# murdock_conn_v3.net
KiCad netlist of a schematic drawn in EAGLE
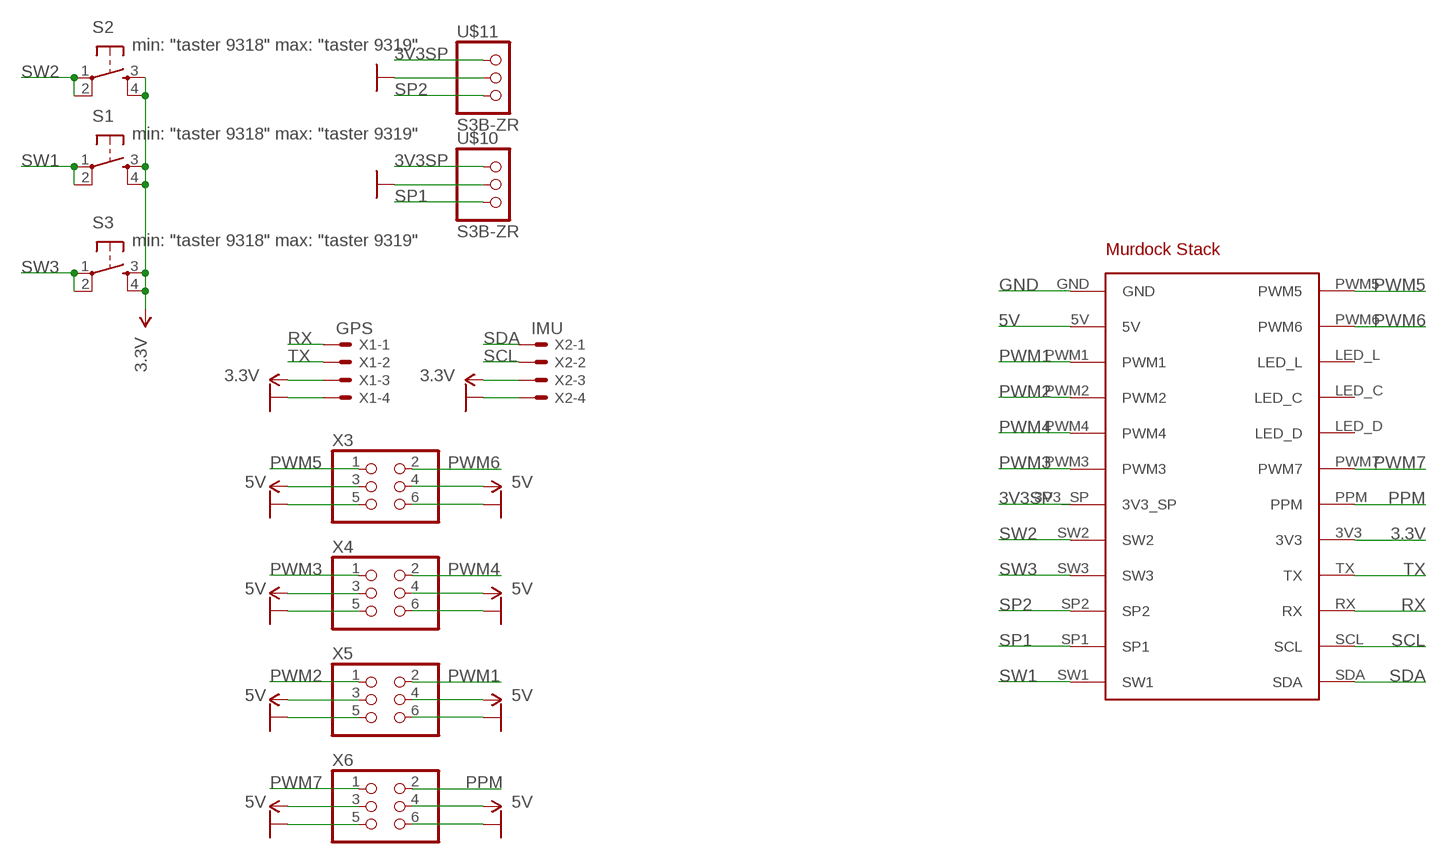
[diagram p0: schematic, sheet 1]

(export (version "E")
  (design (tool "Eeschema 10.0.6"))
  (components
    (comp (ref "S1")
      (value "min: \"taster 9318\" max: \"taster 9319\"")
      (footprint "eagle-import:LSH")
      (libsource (lib "eagle-import") (part "LSH"))
    )
    (comp (ref "S2")
      (value "min: \"taster 9318\" max: \"taster 9319\"")
      (footprint "eagle-import:LSH")
      (libsource (lib "eagle-import") (part "LSH"))
    )
    (comp (ref "S3")
      (value "min: \"taster 9318\" max: \"taster 9319\"")
      (footprint "eagle-import:LSH")
      (libsource (lib "eagle-import") (part "LSH"))
    )
    (comp (ref "U$10")
      (value "S3B-ZR")
      (footprint "eagle-import:S3B-ZR")
      (libsource (lib "eagle-import") (part "S3B-ZR"))
    )
    (comp (ref "U$11")
      (value "S3B-ZR")
      (footprint "eagle-import:S3B-ZR")
      (libsource (lib "eagle-import") (part "S3B-ZR"))
    )
    (comp (ref "X1")
      (value "GPS")
      (footprint "eagle-import:70553-04")
      (libsource (lib "eagle-import") (part "C-GRID-04-70553"))
    )
    (comp (ref "X2")
      (value "IMU")
      (footprint "eagle-import:70553-04")
      (libsource (lib "eagle-import") (part "C-GRID-04-70553"))
    )
    (comp (ref "X3")
      (value "PINHD-2X3/90")
      (footprint "eagle-import:2X03_90")
      (libsource (lib "eagle-import") (part "PINHD-2X3/90"))
    )
    (comp (ref "X4")
      (value "PINHD-2X3/90")
      (footprint "eagle-import:2X03_90")
      (libsource (lib "eagle-import") (part "PINHD-2X3/90"))
    )
    (comp (ref "X5")
      (value "PINHD-2X3/90")
      (footprint "eagle-import:2X03_90")
      (libsource (lib "eagle-import") (part "PINHD-2X3/90"))
    )
    (comp (ref "X6")
      (value "PINHD-2X3/90")
      (footprint "eagle-import:2X03_90")
      (libsource (lib "eagle-import") (part "PINHD-2X3/90"))
    )
    (comp (ref "X7")
      (value "MURDOCK_STACK")
      (footprint "eagle-import:MURDOCK_STACK")
      (libsource (lib "eagle-import") (part "MURDOCK_STACK"))
    )
  )
  (nets
    (net (code "1") (name "/3V3SP") (class "Default")
      (node (ref "U$10") (pin "1") (pinfunction "1_1") (pintype "bidirectional"))
      (node (ref "U$11") (pin "1") (pinfunction "1_1") (pintype "bidirectional"))
      (node (ref "X7") (pin "3V3_SP") (pinfunction "3V3_SP_3V3_SP") (pintype "bidirectional"))
    )
    (net (code "2") (name "/PPM") (class "Default")
      (node (ref "X6") (pin "2") (pinfunction "2_2") (pintype "passive"))
      (node (ref "X7") (pin "PPM") (pinfunction "PPM_PPM") (pintype "bidirectional"))
    )
    (net (code "3") (name "/PWM1") (class "Default")
      (node (ref "X5") (pin "2") (pinfunction "2_2") (pintype "passive"))
      (node (ref "X7") (pin "PWM1") (pinfunction "PWM1_PWM1") (pintype "bidirectional"))
    )
    (net (code "4") (name "/PWM2") (class "Default")
      (node (ref "X5") (pin "1") (pinfunction "1_1") (pintype "passive"))
      (node (ref "X7") (pin "PWM2") (pinfunction "PWM2_PWM2") (pintype "bidirectional"))
    )
    (net (code "5") (name "/PWM3") (class "Default")
      (node (ref "X4") (pin "1") (pinfunction "1_1") (pintype "passive"))
      (node (ref "X7") (pin "PWM3") (pinfunction "PWM3_PWM3") (pintype "bidirectional"))
    )
    (net (code "6") (name "/PWM4") (class "Default")
      (node (ref "X4") (pin "2") (pinfunction "2_2") (pintype "passive"))
      (node (ref "X7") (pin "PWM4") (pinfunction "PWM4_PWM4") (pintype "bidirectional"))
    )
    (net (code "7") (name "/PWM5") (class "Default")
      (node (ref "X3") (pin "1") (pinfunction "1_1") (pintype "passive"))
      (node (ref "X7") (pin "PWM5") (pinfunction "PWM5_PWM5") (pintype "bidirectional"))
    )
    (net (code "8") (name "/PWM6") (class "Default")
      (node (ref "X3") (pin "2") (pinfunction "2_2") (pintype "passive"))
      (node (ref "X7") (pin "PWM6") (pinfunction "PWM6_PWM6") (pintype "bidirectional"))
    )
    (net (code "9") (name "/PWM7") (class "Default")
      (node (ref "X6") (pin "1") (pinfunction "1_1") (pintype "passive"))
      (node (ref "X7") (pin "PWM7") (pinfunction "PWM7_PWM7") (pintype "bidirectional"))
    )
    (net (code "10") (name "/RX") (class "Default")
      (node (ref "X1") (pin "1") (pinfunction "S_1") (pintype "passive"))
      (node (ref "X7") (pin "RX") (pinfunction "RX_RX") (pintype "bidirectional"))
    )
    (net (code "11") (name "/SCL") (class "Default")
      (node (ref "X2") (pin "2") (pinfunction "S_2") (pintype "passive"))
      (node (ref "X7") (pin "SCL") (pinfunction "SCL_SCL") (pintype "bidirectional"))
    )
    (net (code "12") (name "/SDA") (class "Default")
      (node (ref "X2") (pin "1") (pinfunction "S_1") (pintype "passive"))
      (node (ref "X7") (pin "SDA") (pinfunction "SDA_SDA") (pintype "bidirectional"))
    )
    (net (code "13") (name "/SP1") (class "Default")
      (node (ref "U$10") (pin "3") (pinfunction "3_3") (pintype "bidirectional"))
      (node (ref "X7") (pin "SP1") (pinfunction "SP1_SP1") (pintype "bidirectional"))
    )
    (net (code "14") (name "/SP2") (class "Default")
      (node (ref "U$11") (pin "3") (pinfunction "3_3") (pintype "bidirectional"))
      (node (ref "X7") (pin "SP2") (pinfunction "SP2_SP2") (pintype "bidirectional"))
    )
    (net (code "15") (name "/SW1") (class "Default")
      (node (ref "S1") (pin "1") (pinfunction "1_1") (pintype "passive"))
      (node (ref "S1") (pin "2") (pinfunction "2_2") (pintype "passive"))
      (node (ref "X7") (pin "SW1") (pinfunction "SW1_SW1") (pintype "bidirectional"))
    )
    (net (code "16") (name "/SW2") (class "Default")
      (node (ref "S2") (pin "1") (pinfunction "1_1") (pintype "passive"))
      (node (ref "S2") (pin "2") (pinfunction "2_2") (pintype "passive"))
      (node (ref "X7") (pin "SW2") (pinfunction "SW2_SW2") (pintype "bidirectional"))
    )
    (net (code "17") (name "/SW3") (class "Default")
      (node (ref "S3") (pin "1") (pinfunction "1_1") (pintype "passive"))
      (node (ref "S3") (pin "2") (pinfunction "2_2") (pintype "passive"))
      (node (ref "X7") (pin "SW3") (pinfunction "SW3_SW3") (pintype "bidirectional"))
    )
    (net (code "18") (name "/TX") (class "Default")
      (node (ref "X1") (pin "2") (pinfunction "S_2") (pintype "passive"))
      (node (ref "X7") (pin "TX") (pinfunction "TX_TX") (pintype "bidirectional"))
    )
    (net (code "19") (name "3.3V") (class "Default")
      (node (ref "S1") (pin "3") (pinfunction "3_3") (pintype "passive"))
      (node (ref "S1") (pin "4") (pinfunction "4_4") (pintype "passive"))
      (node (ref "S2") (pin "3") (pinfunction "3_3") (pintype "passive"))
      (node (ref "S2") (pin "4") (pinfunction "4_4") (pintype "passive"))
      (node (ref "S3") (pin "3") (pinfunction "3_3") (pintype "passive"))
      (node (ref "S3") (pin "4") (pinfunction "4_4") (pintype "passive"))
      (node (ref "X1") (pin "3") (pinfunction "S_3") (pintype "passive"))
      (node (ref "X2") (pin "3") (pinfunction "S_3") (pintype "passive"))
      (node (ref "X7") (pin "3V3") (pinfunction "3V3_3V3") (pintype "bidirectional"))
    )
    (net (code "20") (name "5V") (class "Default")
      (node (ref "X3") (pin "3") (pinfunction "3_3") (pintype "passive"))
      (node (ref "X3") (pin "4") (pinfunction "4_4") (pintype "passive"))
      (node (ref "X4") (pin "3") (pinfunction "3_3") (pintype "passive"))
      (node (ref "X4") (pin "4") (pinfunction "4_4") (pintype "passive"))
      (node (ref "X5") (pin "3") (pinfunction "3_3") (pintype "passive"))
      (node (ref "X5") (pin "4") (pinfunction "4_4") (pintype "passive"))
      (node (ref "X6") (pin "3") (pinfunction "3_3") (pintype "passive"))
      (node (ref "X6") (pin "4") (pinfunction "4_4") (pintype "passive"))
      (node (ref "X7") (pin "5V") (pinfunction "5V_5V") (pintype "bidirectional"))
    )
    (net (code "21") (name "GND") (class "Default")
      (node (ref "U$10") (pin "2") (pinfunction "2_2") (pintype "bidirectional"))
      (node (ref "U$11") (pin "2") (pinfunction "2_2") (pintype "bidirectional"))
      (node (ref "X1") (pin "4") (pinfunction "S_4") (pintype "passive"))
      (node (ref "X2") (pin "4") (pinfunction "S_4") (pintype "passive"))
      (node (ref "X3") (pin "5") (pinfunction "5_5") (pintype "passive"))
      (node (ref "X3") (pin "6") (pinfunction "6_6") (pintype "passive"))
      (node (ref "X4") (pin "5") (pinfunction "5_5") (pintype "passive"))
      (node (ref "X4") (pin "6") (pinfunction "6_6") (pintype "passive"))
      (node (ref "X5") (pin "5") (pinfunction "5_5") (pintype "passive"))
      (node (ref "X5") (pin "6") (pinfunction "6_6") (pintype "passive"))
      (node (ref "X6") (pin "5") (pinfunction "5_5") (pintype "passive"))
      (node (ref "X6") (pin "6") (pinfunction "6_6") (pintype "passive"))
      (node (ref "X7") (pin "GND") (pinfunction "GND_GND") (pintype "bidirectional"))
    )
    (net (code "22") (name "unconnected-(X7-PadLED_C)") (class "Default")
      (node (ref "X7") (pin "LED_C") (pinfunction "LED_C_LED_C") (pintype "bidirectional"))
    )
    (net (code "23") (name "unconnected-(X7-PadLED_D)") (class "Default")
      (node (ref "X7") (pin "LED_D") (pinfunction "LED_D_LED_D") (pintype "bidirectional"))
    )
    (net (code "24") (name "unconnected-(X7-PadLED_L)") (class "Default")
      (node (ref "X7") (pin "LED_L") (pinfunction "LED_L_LED_L") (pintype "bidirectional"))
    )
  )
)
